# core.net
KiCad netlist of a schematic drawn in Altium Designer
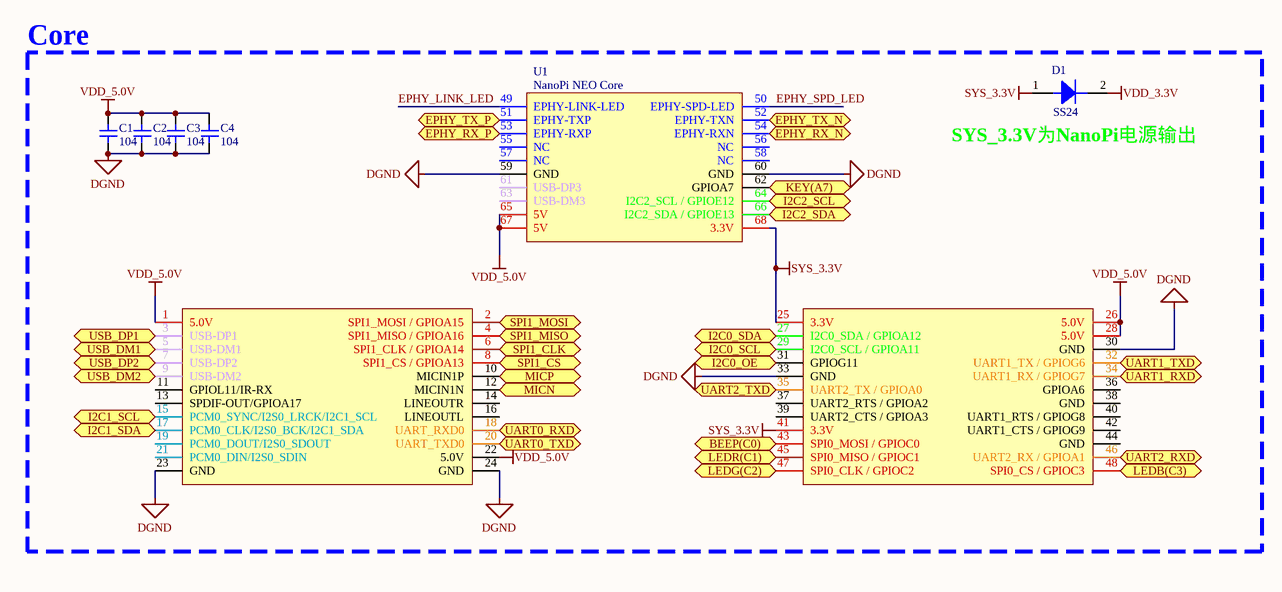
[diagram p0: core.SchDoc]

(export (version "E")
  (design (tool "Eeschema 10.0.6"))
  (components
    (comp (ref "C1")
      (value "104")
      (footprint "0805C")
      (description "无极贴片电容")
      (libsource (lib "集大电协1.5") (part "Cap1"))
    )
    (comp (ref "C2")
      (value "104")
      (footprint "0805C")
      (description "无极贴片电容")
      (libsource (lib "集大电协1.5") (part "Cap1"))
    )
    (comp (ref "C3")
      (value "104")
      (footprint "0805C")
      (description "无极贴片电容")
      (libsource (lib "集大电协1.5") (part "Cap1"))
    )
    (comp (ref "C4")
      (value "104")
      (footprint "0805C")
      (description "无极贴片电容")
      (libsource (lib "集大电协1.5") (part "Cap1"))
    )
    (comp (ref "D1")
      (value "SS24")
      (footprint "SMA/DO-214AC")
      (description "二极管")
      (libsource (lib "集大电协1.5") (part "Diode"))
    )
    (comp (ref "U1")
      (value "NanoPi NEO Core")
      (footprint "NanoPi NEO Core")
      (libsource (lib "集大电协1.5") (part "NanoPi NEO Core"))
    )
  )
  (nets
    (net (code "1") (name "/BEEP(C0)") (class "Default")
      (node (ref "U1") (pin "43") (pinfunction "SPI0_MOSI_/_GPIOC0_43") (pintype "passive"))
    )
    (net (code "2") (name "/EPHY_LINK_LED") (class "Default")
      (node (ref "U1") (pin "49") (pinfunction "EPHY-LINK-LED_49") (pintype "passive"))
    )
    (net (code "3") (name "/EPHY_RX_N") (class "Default")
      (node (ref "U1") (pin "54") (pinfunction "EPHY-RXN_54") (pintype "passive"))
    )
    (net (code "4") (name "/EPHY_RX_P") (class "Default")
      (node (ref "U1") (pin "53") (pinfunction "EPHY-RXP_53") (pintype "passive"))
    )
    (net (code "5") (name "/EPHY_SPD_LED") (class "Default")
      (node (ref "U1") (pin "50") (pinfunction "EPHY-SPD-LED_50") (pintype "passive"))
    )
    (net (code "6") (name "/EPHY_TX_N") (class "Default")
      (node (ref "U1") (pin "52") (pinfunction "EPHY-TXN_52") (pintype "passive"))
    )
    (net (code "7") (name "/EPHY_TX_P") (class "Default")
      (node (ref "U1") (pin "51") (pinfunction "EPHY-TXP_51") (pintype "passive"))
    )
    (net (code "8") (name "/I2C0_OE") (class "Default")
      (node (ref "U1") (pin "31") (pinfunction "GPIOG11_31") (pintype "passive"))
    )
    (net (code "9") (name "/I2C0_SCL") (class "Default")
      (node (ref "U1") (pin "29") (pinfunction "I2C0_SCL_/_GPIOA11_29") (pintype "passive"))
    )
    (net (code "10") (name "/I2C0_SDA") (class "Default")
      (node (ref "U1") (pin "27") (pinfunction "I2C0_SDA_/_GPIOA12_27") (pintype "passive"))
    )
    (net (code "11") (name "/I2C1_SCL") (class "Default")
      (node (ref "U1") (pin "15") (pinfunction "PCM0_SYNC/I2S0_LRCK/I2C1_SCL_15") (pintype "passive"))
    )
    (net (code "12") (name "/I2C1_SDA") (class "Default")
      (node (ref "U1") (pin "17") (pinfunction "PCM0_CLK/I2S0_BCK/I2C1_SDA_17") (pintype "passive"))
    )
    (net (code "13") (name "/I2C2_SCL") (class "Default")
      (node (ref "U1") (pin "64") (pinfunction "I2C2_SCL_/_GPIOE12_64") (pintype "passive"))
    )
    (net (code "14") (name "/I2C2_SDA") (class "Default")
      (node (ref "U1") (pin "66") (pinfunction "I2C2_SDA_/_GPIOE13_66") (pintype "passive"))
    )
    (net (code "15") (name "/KEY(A7)") (class "Default")
      (node (ref "U1") (pin "62") (pinfunction "GPIOA7_62") (pintype "passive"))
    )
    (net (code "16") (name "/LEDB(C3)") (class "Default")
      (node (ref "U1") (pin "48") (pinfunction "SPI0_CS_/_GPIOC3_48") (pintype "passive"))
    )
    (net (code "17") (name "/LEDG(C2)") (class "Default")
      (node (ref "U1") (pin "47") (pinfunction "SPI0_CLK_/_GPIOC2_47") (pintype "passive"))
    )
    (net (code "18") (name "/LEDR(C1)") (class "Default")
      (node (ref "U1") (pin "45") (pinfunction "SPI0_MISO_/_GPIOC1_45") (pintype "passive"))
    )
    (net (code "19") (name "/MICN") (class "Default")
      (node (ref "U1") (pin "12") (pinfunction "MICIN1N_12") (pintype "passive"))
    )
    (net (code "20") (name "/MICP") (class "Default")
      (node (ref "U1") (pin "10") (pinfunction "MICIN1P_10") (pintype "passive"))
    )
    (net (code "21") (name "/SPI1_CLK") (class "Default")
      (node (ref "U1") (pin "6") (pinfunction "SPI1_CLK_/_GPIOA14_6") (pintype "passive"))
    )
    (net (code "22") (name "/SPI1_CS") (class "Default")
      (node (ref "U1") (pin "8") (pinfunction "SPI1_CS_/_GPIOA13_8") (pintype "passive"))
    )
    (net (code "23") (name "/SPI1_MISO") (class "Default")
      (node (ref "U1") (pin "4") (pinfunction "SPI1_MISO_/_GPIOA16_4") (pintype "passive"))
    )
    (net (code "24") (name "/SPI1_MOSI") (class "Default")
      (node (ref "U1") (pin "2") (pinfunction "SPI1_MOSI_/_GPIOA15_2") (pintype "passive"))
    )
    (net (code "25") (name "/UART0_RXD") (class "Default")
      (node (ref "U1") (pin "18") (pinfunction "UART_RXD0_18") (pintype "passive"))
    )
    (net (code "26") (name "/UART0_TXD") (class "Default")
      (node (ref "U1") (pin "20") (pinfunction "UART_TXD0_20") (pintype "passive"))
    )
    (net (code "27") (name "/UART1_RXD") (class "Default")
      (node (ref "U1") (pin "34") (pinfunction "UART1_RX_/_GPIOG7_34") (pintype "passive"))
    )
    (net (code "28") (name "/UART1_TXD") (class "Default")
      (node (ref "U1") (pin "32") (pinfunction "UART1_TX_/_GPIOG6_32") (pintype "passive"))
    )
    (net (code "29") (name "/UART2_RXD") (class "Default")
      (node (ref "U1") (pin "46") (pinfunction "UART2_RX_/_GPIOA1_46") (pintype "passive"))
    )
    (net (code "30") (name "/UART2_TXD") (class "Default")
      (node (ref "U1") (pin "35") (pinfunction "UART2_TX_/_GPIOA0_35") (pintype "passive"))
    )
    (net (code "31") (name "/USB_DM1") (class "Default")
      (node (ref "U1") (pin "5") (pinfunction "USB-DM1_5") (pintype "passive"))
    )
    (net (code "32") (name "/USB_DM2") (class "Default")
      (node (ref "U1") (pin "9") (pinfunction "USB-DM2_9") (pintype "passive"))
    )
    (net (code "33") (name "/USB_DP1") (class "Default")
      (node (ref "U1") (pin "3") (pinfunction "USB-DP1_3") (pintype "passive"))
    )
    (net (code "34") (name "/USB_DP2") (class "Default")
      (node (ref "U1") (pin "7") (pinfunction "USB-DP2_7") (pintype "passive"))
    )
    (net (code "35") (name "DGND") (class "Default")
      (node (ref "C1") (pin "1") (pinfunction "1_1") (pintype "passive"))
      (node (ref "C2") (pin "1") (pinfunction "1_1") (pintype "passive"))
      (node (ref "C3") (pin "1") (pinfunction "1_1") (pintype "passive"))
      (node (ref "C4") (pin "1") (pinfunction "1_1") (pintype "passive"))
      (node (ref "U1") (pin "23") (pinfunction "GND_23") (pintype "passive"))
      (node (ref "U1") (pin "24") (pinfunction "GND_24") (pintype "passive"))
      (node (ref "U1") (pin "30") (pinfunction "GND_30") (pintype "passive"))
      (node (ref "U1") (pin "33") (pinfunction "GND_33") (pintype "passive"))
      (node (ref "U1") (pin "59") (pinfunction "GND_59") (pintype "passive"))
      (node (ref "U1") (pin "60") (pinfunction "GND_60") (pintype "passive"))
    )
    (net (code "36") (name "SYS_3.3V") (class "Default")
      (node (ref "D1") (pin "1") (pintype "passive"))
      (node (ref "U1") (pin "25") (pinfunction "3.3V_25") (pintype "passive"))
      (node (ref "U1") (pin "41") (pinfunction "3.3V_41") (pintype "passive"))
      (node (ref "U1") (pin "68") (pinfunction "3.3V_68") (pintype "passive"))
    )
    (net (code "37") (name "VDD_3.3V") (class "Default")
      (node (ref "D1") (pin "2") (pinfunction "2_2") (pintype "passive"))
    )
    (net (code "38") (name "VDD_5.0V") (class "Default")
      (node (ref "C1") (pin "2") (pinfunction "2_2") (pintype "passive"))
      (node (ref "C2") (pin "2") (pinfunction "2_2") (pintype "passive"))
      (node (ref "C3") (pin "2") (pinfunction "2_2") (pintype "passive"))
      (node (ref "C4") (pin "2") (pinfunction "2_2") (pintype "passive"))
      (node (ref "U1") (pin "1") (pinfunction "5.0V_1") (pintype "passive"))
      (node (ref "U1") (pin "22") (pinfunction "5.0V_22") (pintype "passive"))
      (node (ref "U1") (pin "26") (pinfunction "5.0V_26") (pintype "passive"))
      (node (ref "U1") (pin "28") (pinfunction "5.0V_28") (pintype "passive"))
      (node (ref "U1") (pin "65") (pinfunction "5V_65") (pintype "passive"))
      (node (ref "U1") (pin "67") (pinfunction "5V_67") (pintype "passive"))
    )
    (net (code "39") (name "unconnected-(U1-GND-Pad38)") (class "Default")
      (node (ref "U1") (pin "38") (pinfunction "GND_38") (pintype "passive"))
    )
    (net (code "40") (name "unconnected-(U1-GND-Pad44)") (class "Default")
      (node (ref "U1") (pin "44") (pinfunction "GND_44") (pintype "passive"))
    )
    (net (code "41") (name "unconnected-(U1-GPIOA6-Pad36)") (class "Default")
      (node (ref "U1") (pin "36") (pinfunction "GPIOA6_36") (pintype "passive"))
    )
    (net (code "42") (name "unconnected-(U1-GPIOL11{slash}IR-RX-Pad11)") (class "Default")
      (node (ref "U1") (pin "11") (pinfunction "GPIOL11/IR-RX_11") (pintype "passive"))
    )
    (net (code "43") (name "unconnected-(U1-LINEOUTL-Pad16)") (class "Default")
      (node (ref "U1") (pin "16") (pinfunction "LINEOUTL_16") (pintype "passive"))
    )
    (net (code "44") (name "unconnected-(U1-LINEOUTR-Pad14)") (class "Default")
      (node (ref "U1") (pin "14") (pinfunction "LINEOUTR_14") (pintype "passive"))
    )
    (net (code "45") (name "unconnected-(U1-NC-Pad55)") (class "Default")
      (node (ref "U1") (pin "55") (pinfunction "NC_55") (pintype "passive"))
    )
    (net (code "46") (name "unconnected-(U1-NC-Pad56)") (class "Default")
      (node (ref "U1") (pin "56") (pinfunction "NC_56") (pintype "passive"))
    )
    (net (code "47") (name "unconnected-(U1-NC-Pad57)") (class "Default")
      (node (ref "U1") (pin "57") (pinfunction "NC_57") (pintype "passive"))
    )
    (net (code "48") (name "unconnected-(U1-NC-Pad58)") (class "Default")
      (node (ref "U1") (pin "58") (pinfunction "NC_58") (pintype "passive"))
    )
    (net (code "49") (name "unconnected-(U1-PCM0_DIN{slash}I2S0_SDIN-Pad21)") (class "Default")
      (node (ref "U1") (pin "21") (pinfunction "PCM0_DIN/I2S0_SDIN_21") (pintype "passive"))
    )
    (net (code "50") (name "unconnected-(U1-PCM0_DOUT{slash}I2S0_SDOUT-Pad19)") (class "Default")
      (node (ref "U1") (pin "19") (pinfunction "PCM0_DOUT/I2S0_SDOUT_19") (pintype "passive"))
    )
    (net (code "51") (name "unconnected-(U1-SPDIF-OUT{slash}GPIOA17-Pad13)") (class "Default")
      (node (ref "U1") (pin "13") (pinfunction "SPDIF-OUT/GPIOA17_13") (pintype "passive"))
    )
    (net (code "52") (name "unconnected-(U1-UART1_CTS_{slash}_GPIOG9-Pad42)") (class "Default")
      (node (ref "U1") (pin "42") (pinfunction "UART1_CTS_/_GPIOG9_42") (pintype "passive"))
    )
    (net (code "53") (name "unconnected-(U1-UART1_RTS_{slash}_GPIOG8-Pad40)") (class "Default")
      (node (ref "U1") (pin "40") (pinfunction "UART1_RTS_/_GPIOG8_40") (pintype "passive"))
    )
    (net (code "54") (name "unconnected-(U1-UART2_CTS_{slash}_GPIOA3-Pad39)") (class "Default")
      (node (ref "U1") (pin "39") (pinfunction "UART2_CTS_/_GPIOA3_39") (pintype "passive"))
    )
    (net (code "55") (name "unconnected-(U1-UART2_RTS_{slash}_GPIOA2-Pad37)") (class "Default")
      (node (ref "U1") (pin "37") (pinfunction "UART2_RTS_/_GPIOA2_37") (pintype "passive"))
    )
    (net (code "56") (name "unconnected-(U1-USB-DM3-Pad63)") (class "Default")
      (node (ref "U1") (pin "63") (pinfunction "USB-DM3_63") (pintype "passive"))
    )
    (net (code "57") (name "unconnected-(U1-USB-DP3-Pad61)") (class "Default")
      (node (ref "U1") (pin "61") (pinfunction "USB-DP3_61") (pintype "passive"))
    )
  )
)
